# PIC32MK.net
KiCad netlist of a schematic drawn in Altium Designer
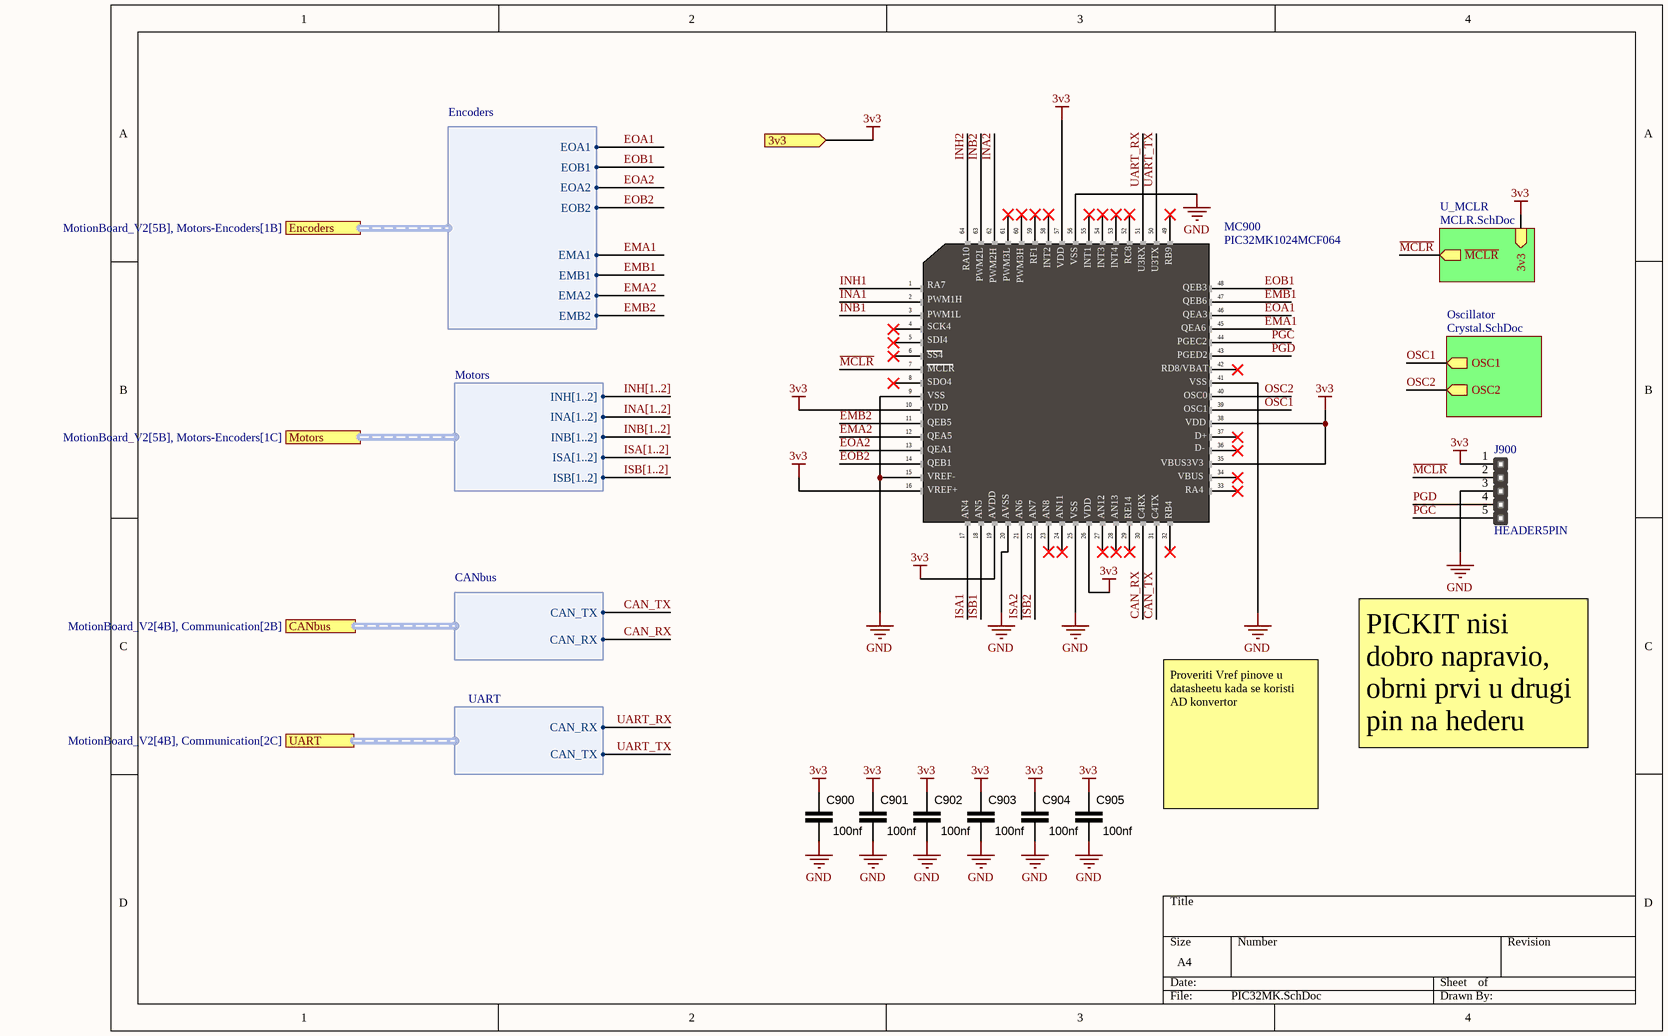
[diagram p0: PIC32MK.SchDoc]

(export (version "E")
  (design (tool "Eeschema 10.0.6"))
  (components
    (comp (ref "C900")
      (value "100nf")
      (footprint "CAP_0603")
      (description "CAP CER 100nF 0603 25V X7R")
      (libsource (lib "CapacitorsIntegrated") (part "C000007"))
    )
    (comp (ref "C901")
      (value "100nf")
      (footprint "CAP_0603")
      (description "CAP CER 100nF 0603 25V X7R")
      (libsource (lib "CapacitorsIntegrated") (part "C000007"))
    )
    (comp (ref "C902")
      (value "100nf")
      (footprint "CAP_0603")
      (description "CAP CER 100nF 0603 25V X7R")
      (libsource (lib "CapacitorsIntegrated") (part "C000007"))
    )
    (comp (ref "C903")
      (value "100nf")
      (footprint "CAP_0603")
      (description "CAP CER 100nF 0603 25V X7R")
      (libsource (lib "CapacitorsIntegrated") (part "C000007"))
    )
    (comp (ref "C904")
      (value "100nf")
      (footprint "CAP_0603")
      (description "CAP CER 100nF 0603 25V X7R")
      (libsource (lib "CapacitorsIntegrated") (part "C000007"))
    )
    (comp (ref "C905")
      (value "100nf")
      (footprint "CAP_0603")
      (description "CAP CER 100nF 0603 25V X7R")
      (libsource (lib "CapacitorsIntegrated") (part "C000007"))
    )
    (comp (ref "J900")
      (value "HEADER5PIN")
      (footprint "Connectors:HEADER5PIN")
      (description "5 PIN Male Header 2.54mm pitch")
      (libsource (lib "Connectors") (part "HEADER5PIN"))
    )
    (comp (ref "MC900")
      (value "PIC32MK1024MCF064")
      (footprint "MicroControllers:PIC32MK_64-TQFP")
      (description "PIC32 Motor Control Microcontroller\r\nPIC32MK1024MCF064\r\nPIC32MK1024MCM064\r\nCompatible")
      (libsource (lib "MicroControllers") (part "PIC32MK"))
    )
  )
  (nets
    (net (code "5") (name "/CAN_RX") (class "Default")
      (node (ref "MC900") (pin "30") (pinfunction "30_30") (pintype "passive"))
    )
    (net (code "6") (name "/CAN_TX") (class "Default")
      (node (ref "MC900") (pin "31") (pinfunction "31_31") (pintype "passive"))
    )
    (net (code "7") (name "/EMA1") (class "Default")
      (node (ref "MC900") (pin "45") (pinfunction "45_45") (pintype "passive"))
    )
    (net (code "8") (name "/EMA2") (class "Default")
      (node (ref "MC900") (pin "12") (pinfunction "12_12") (pintype "passive"))
    )
    (net (code "9") (name "/EMB1") (class "Default")
      (node (ref "MC900") (pin "47") (pinfunction "47_47") (pintype "passive"))
    )
    (net (code "10") (name "/EMB2") (class "Default")
      (node (ref "MC900") (pin "11") (pinfunction "11_11") (pintype "passive"))
    )
    (net (code "11") (name "/EOA1") (class "Default")
      (node (ref "MC900") (pin "46") (pinfunction "46_46") (pintype "passive"))
    )
    (net (code "12") (name "/EOA2") (class "Default")
      (node (ref "MC900") (pin "13") (pinfunction "13_13") (pintype "passive"))
    )
    (net (code "13") (name "/EOB1") (class "Default")
      (node (ref "MC900") (pin "48") (pinfunction "48_48") (pintype "passive"))
    )
    (net (code "14") (name "/EOB2") (class "Default")
      (node (ref "MC900") (pin "14") (pinfunction "14_14") (pintype "passive"))
    )
    (net (code "15") (name "/INA1") (class "Default")
      (node (ref "MC900") (pin "2") (pinfunction "2_2") (pintype "passive"))
    )
    (net (code "16") (name "/INA2") (class "Default")
      (node (ref "MC900") (pin "62") (pinfunction "62_62") (pintype "passive"))
    )
    (net (code "18") (name "/INB1") (class "Default")
      (node (ref "MC900") (pin "3") (pinfunction "3_3") (pintype "passive"))
    )
    (net (code "19") (name "/INB2") (class "Default")
      (node (ref "MC900") (pin "63") (pinfunction "63_63") (pintype "passive"))
    )
    (net (code "21") (name "/INH1") (class "Default")
      (node (ref "MC900") (pin "1") (pinfunction "1_1") (pintype "passive"))
    )
    (net (code "22") (name "/INH2") (class "Default")
      (node (ref "MC900") (pin "64") (pinfunction "64_64") (pintype "passive"))
    )
    (net (code "24") (name "/ISA1") (class "Default")
      (node (ref "MC900") (pin "17") (pinfunction "17_17") (pintype "passive"))
    )
    (net (code "25") (name "/ISA2") (class "Default")
      (node (ref "MC900") (pin "21") (pinfunction "21_21") (pintype "passive"))
    )
    (net (code "27") (name "/ISB1") (class "Default")
      (node (ref "MC900") (pin "18") (pinfunction "18_18") (pintype "passive"))
    )
    (net (code "28") (name "/ISB2") (class "Default")
      (node (ref "MC900") (pin "22") (pinfunction "22_22") (pintype "passive"))
    )
    (net (code "30") (name "/OSC1") (class "Default")
      (node (ref "MC900") (pin "39") (pinfunction "39_39") (pintype "passive"))
    )
    (net (code "31") (name "/OSC2") (class "Default")
      (node (ref "MC900") (pin "40") (pinfunction "40_40") (pintype "passive"))
    )
    (net (code "32") (name "/PGC") (class "Default")
      (node (ref "J900") (pin "5") (pinfunction "5_5") (pintype "passive"))
      (node (ref "MC900") (pin "44") (pinfunction "44_44") (pintype "passive"))
    )
    (net (code "33") (name "/PGD") (class "Default")
      (node (ref "J900") (pin "4") (pinfunction "4_4") (pintype "passive"))
      (node (ref "MC900") (pin "43") (pinfunction "43_43") (pintype "passive"))
    )
    (net (code "34") (name "/UART_RX") (class "Default")
      (node (ref "MC900") (pin "51") (pinfunction "51_51") (pintype "passive"))
    )
    (net (code "35") (name "/UART_TX") (class "Default")
      (node (ref "MC900") (pin "50") (pinfunction "50_50") (pintype "passive"))
    )
    (net (code "40") (name "/~{MCLR}") (class "Default")
      (node (ref "J900") (pin "2") (pinfunction "1_2") (pintype "passive"))
      (node (ref "MC900") (pin "7") (pinfunction "7_7") (pintype "passive"))
    )
    (net (code "41") (name "3v3") (class "Default")
      (node (ref "C900") (pin "2") (pinfunction "2_2") (pintype "passive"))
      (node (ref "C901") (pin "2") (pinfunction "2_2") (pintype "passive"))
      (node (ref "C902") (pin "2") (pinfunction "2_2") (pintype "passive"))
      (node (ref "C903") (pin "2") (pinfunction "2_2") (pintype "passive"))
      (node (ref "C904") (pin "2") (pinfunction "2_2") (pintype "passive"))
      (node (ref "C905") (pin "2") (pinfunction "2_2") (pintype "passive"))
      (node (ref "J900") (pin "1") (pinfunction "1_1") (pintype "passive"))
      (node (ref "MC900") (pin "10") (pinfunction "10_10") (pintype "passive"))
      (node (ref "MC900") (pin "16") (pinfunction "16_16") (pintype "passive"))
      (node (ref "MC900") (pin "19") (pinfunction "19_19") (pintype "passive"))
      (node (ref "MC900") (pin "26") (pinfunction "26_26") (pintype "passive"))
      (node (ref "MC900") (pin "35") (pinfunction "35_35") (pintype "passive"))
      (node (ref "MC900") (pin "38") (pinfunction "38_38") (pintype "passive"))
      (node (ref "MC900") (pin "57") (pinfunction "57_57") (pintype "passive"))
    )
    (net (code "42") (name "GND") (class "Default")
      (node (ref "C900") (pin "1") (pinfunction "1_1") (pintype "passive"))
      (node (ref "C901") (pin "1") (pinfunction "1_1") (pintype "passive"))
      (node (ref "C902") (pin "1") (pinfunction "1_1") (pintype "passive"))
      (node (ref "C903") (pin "1") (pinfunction "1_1") (pintype "passive"))
      (node (ref "C904") (pin "1") (pinfunction "1_1") (pintype "passive"))
      (node (ref "C905") (pin "1") (pinfunction "1_1") (pintype "passive"))
      (node (ref "J900") (pin "3") (pinfunction "1_3") (pintype "passive"))
      (node (ref "MC900") (pin "15") (pinfunction "15_15") (pintype "passive"))
      (node (ref "MC900") (pin "20") (pinfunction "20_20") (pintype "passive"))
      (node (ref "MC900") (pin "25") (pinfunction "25_25") (pintype "passive"))
      (node (ref "MC900") (pin "41") (pinfunction "41_41") (pintype "passive"))
      (node (ref "MC900") (pin "56") (pinfunction "56_56") (pintype "passive"))
      (node (ref "MC900") (pin "9") (pinfunction "9_9") (pintype "passive"))
    )
    (net (code "43") (name "unconnected-(MC900-Pad4)") (class "Default")
      (node (ref "MC900") (pin "4") (pinfunction "4_4") (pintype "passive+no_connect"))
    )
    (net (code "44") (name "unconnected-(MC900-Pad5)") (class "Default")
      (node (ref "MC900") (pin "5") (pinfunction "5_5") (pintype "passive+no_connect"))
    )
    (net (code "45") (name "unconnected-(MC900-Pad6)") (class "Default")
      (node (ref "MC900") (pin "6") (pinfunction "6_6") (pintype "passive+no_connect"))
    )
    (net (code "46") (name "unconnected-(MC900-Pad8)") (class "Default")
      (node (ref "MC900") (pin "8") (pinfunction "8_8") (pintype "passive+no_connect"))
    )
    (net (code "47") (name "unconnected-(MC900-Pad23)") (class "Default")
      (node (ref "MC900") (pin "23") (pinfunction "23_23") (pintype "passive+no_connect"))
    )
    (net (code "48") (name "unconnected-(MC900-Pad24)") (class "Default")
      (node (ref "MC900") (pin "24") (pinfunction "24_24") (pintype "passive+no_connect"))
    )
    (net (code "49") (name "unconnected-(MC900-Pad27)") (class "Default")
      (node (ref "MC900") (pin "27") (pinfunction "27_27") (pintype "passive+no_connect"))
    )
    (net (code "50") (name "unconnected-(MC900-Pad28)") (class "Default")
      (node (ref "MC900") (pin "28") (pinfunction "28_28") (pintype "passive+no_connect"))
    )
    (net (code "51") (name "unconnected-(MC900-Pad29)") (class "Default")
      (node (ref "MC900") (pin "29") (pinfunction "29_29") (pintype "passive+no_connect"))
    )
    (net (code "52") (name "unconnected-(MC900-Pad32)") (class "Default")
      (node (ref "MC900") (pin "32") (pinfunction "32_32") (pintype "passive+no_connect"))
    )
    (net (code "53") (name "unconnected-(MC900-Pad33)") (class "Default")
      (node (ref "MC900") (pin "33") (pinfunction "33_33") (pintype "passive+no_connect"))
    )
    (net (code "54") (name "unconnected-(MC900-Pad34)") (class "Default")
      (node (ref "MC900") (pin "34") (pinfunction "34_34") (pintype "passive+no_connect"))
    )
    (net (code "55") (name "unconnected-(MC900-Pad36)") (class "Default")
      (node (ref "MC900") (pin "36") (pinfunction "36_36") (pintype "passive+no_connect"))
    )
    (net (code "56") (name "unconnected-(MC900-Pad37)") (class "Default")
      (node (ref "MC900") (pin "37") (pinfunction "37_37") (pintype "passive+no_connect"))
    )
    (net (code "57") (name "unconnected-(MC900-Pad42)") (class "Default")
      (node (ref "MC900") (pin "42") (pinfunction "42_42") (pintype "passive+no_connect"))
    )
    (net (code "58") (name "unconnected-(MC900-Pad49)") (class "Default")
      (node (ref "MC900") (pin "49") (pinfunction "49_49") (pintype "passive+no_connect"))
    )
    (net (code "59") (name "unconnected-(MC900-Pad52)") (class "Default")
      (node (ref "MC900") (pin "52") (pinfunction "52_52") (pintype "passive+no_connect"))
    )
    (net (code "60") (name "unconnected-(MC900-Pad53)") (class "Default")
      (node (ref "MC900") (pin "53") (pinfunction "53_53") (pintype "passive+no_connect"))
    )
    (net (code "61") (name "unconnected-(MC900-Pad54)") (class "Default")
      (node (ref "MC900") (pin "54") (pinfunction "54_54") (pintype "passive+no_connect"))
    )
    (net (code "62") (name "unconnected-(MC900-Pad55)") (class "Default")
      (node (ref "MC900") (pin "55") (pinfunction "55_55") (pintype "passive+no_connect"))
    )
    (net (code "63") (name "unconnected-(MC900-Pad58)") (class "Default")
      (node (ref "MC900") (pin "58") (pinfunction "58_58") (pintype "passive+no_connect"))
    )
    (net (code "64") (name "unconnected-(MC900-Pad59)") (class "Default")
      (node (ref "MC900") (pin "59") (pinfunction "59_59") (pintype "passive+no_connect"))
    )
    (net (code "65") (name "unconnected-(MC900-Pad60)") (class "Default")
      (node (ref "MC900") (pin "60") (pinfunction "60_60") (pintype "passive+no_connect"))
    )
    (net (code "66") (name "unconnected-(MC900-Pad61)") (class "Default")
      (node (ref "MC900") (pin "61") (pinfunction "61_61") (pintype "passive+no_connect"))
    )
  )
)
